# EnvironmentOnAStickV2.net
KiCad netlist of a schematic drawn in EAGLE
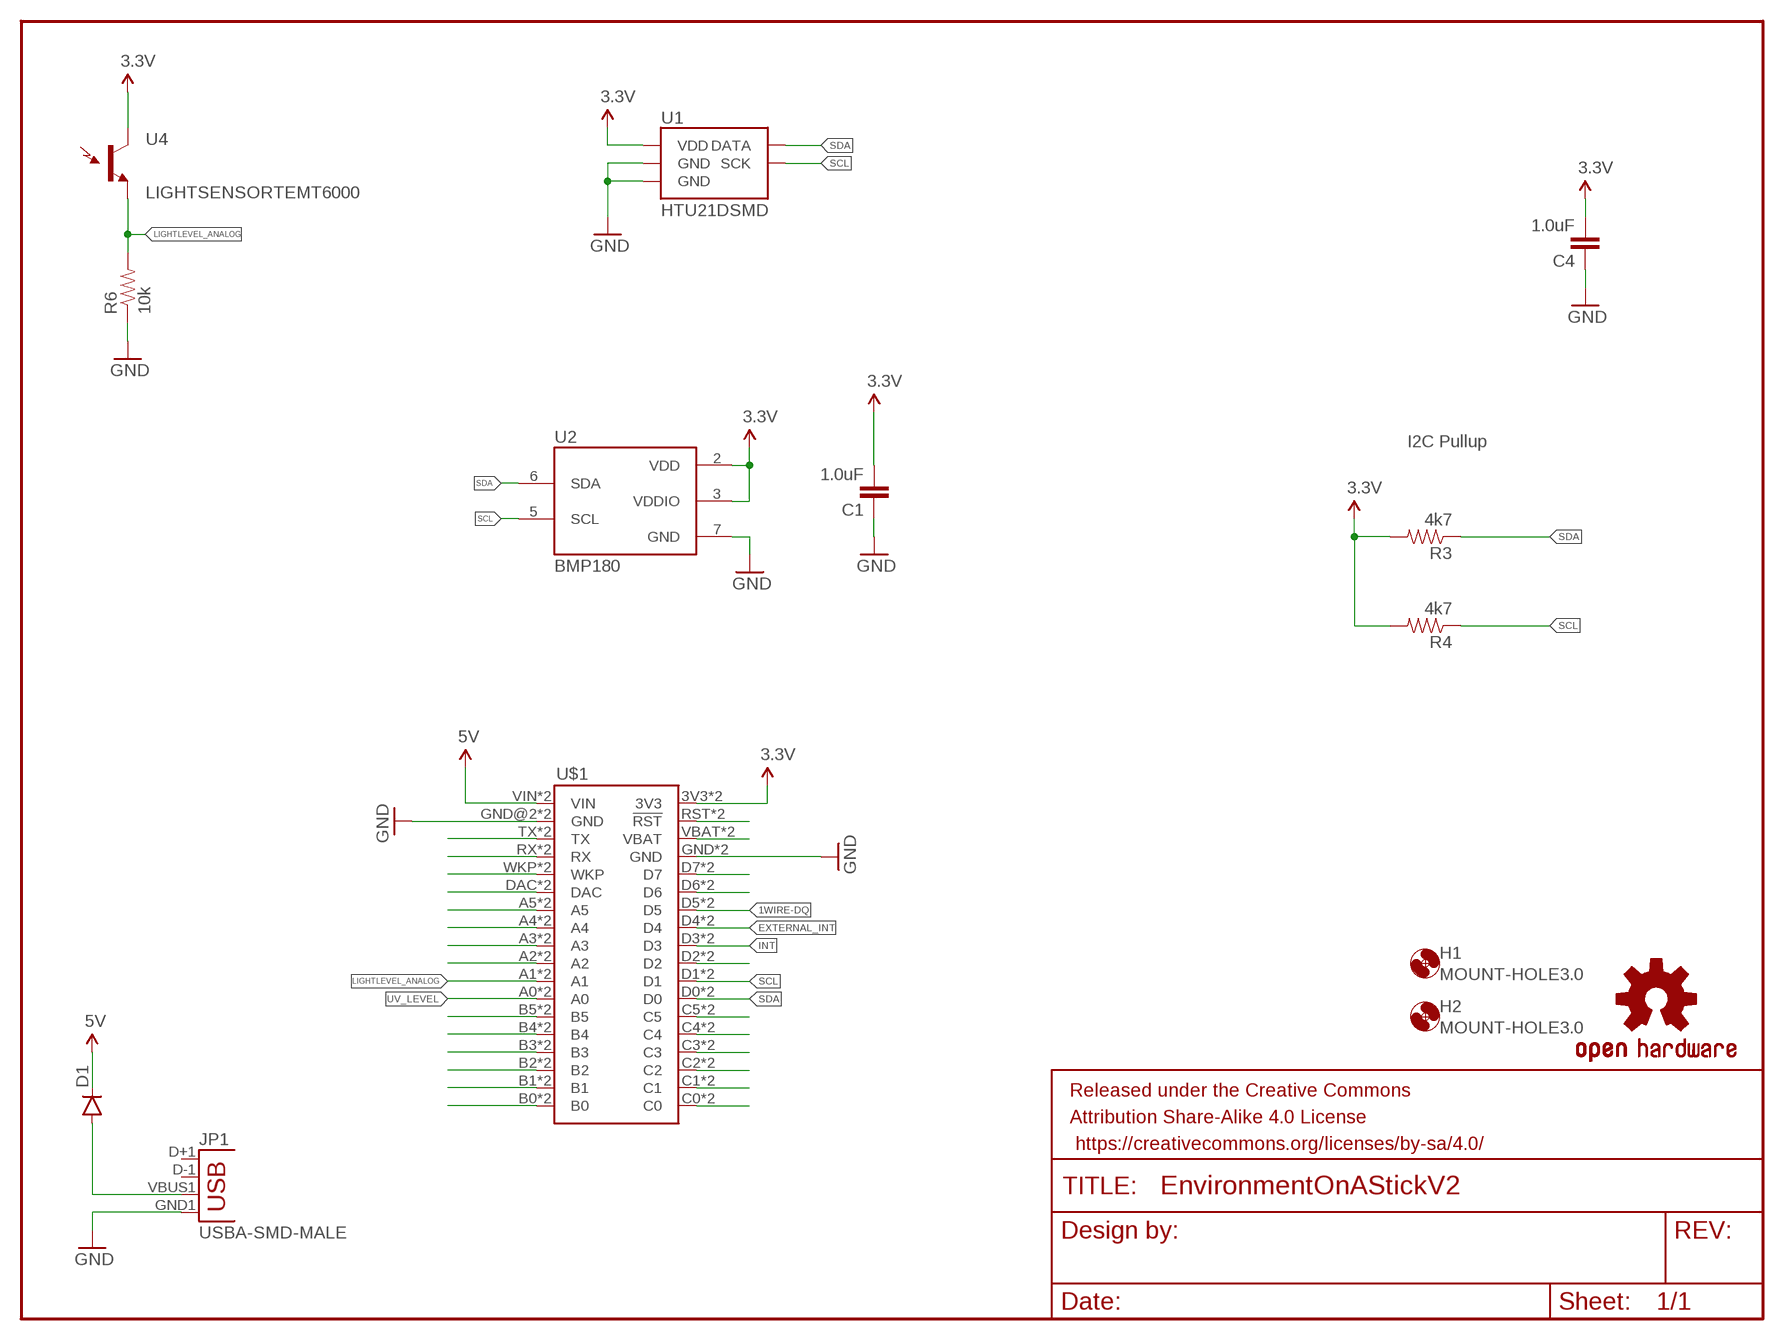
[diagram p0: schematic, sheet 1]

(export (version "E")
  (design (tool "Eeschema 10.0.6"))
  (components
    (comp (ref "C1")
      (value "1.0uF")
      (footprint "eagle-import:0805-CAP")
      (libsource (lib "eagle-import") (part "1.0UF-25V-+80/-20(0805){dblquote}"))
    )
    (comp (ref "C4")
      (value "1.0uF")
      (footprint "eagle-import:0805-CAP")
      (libsource (lib "eagle-import") (part "1.0UF-25V-+80/-20(0805){dblquote}"))
    )
    (comp (ref "D1")
      (value "DIODESMA")
      (footprint "eagle-import:SMA-DIODE")
      (libsource (lib "eagle-import") (part "DIODESMA"))
    )
    (comp (ref "FRAME1")
      (value "FRAME-LETTER")
      (footprint "eagle-import:CREATIVE_COMMONS")
      (libsource (lib "eagle-import") (part "FRAME-LETTER"))
    )
    (comp (ref "H1")
      (value "MOUNT-HOLE3.0")
      (footprint "eagle-import:3,0")
      (libsource (lib "eagle-import") (part "MOUNT-HOLE3.0"))
    )
    (comp (ref "H2")
      (value "MOUNT-HOLE3.0")
      (footprint "eagle-import:3,0")
      (libsource (lib "eagle-import") (part "MOUNT-HOLE3.0"))
    )
    (comp (ref "JP1")
      (value "USBA-SMD-MALE")
      (footprint "eagle-import:USB-A-SMT-MALE")
      (libsource (lib "eagle-import") (part "USBA-SMD-MALE"))
    )
    (comp (ref "LOGO1")
      (value "OSHW-LOGOM")
      (footprint "eagle-import:OSHW-LOGO-M")
      (libsource (lib "eagle-import") (part "OSHW-LOGOM"))
    )
    (comp (ref "R3")
      (value "4k7")
      (footprint "eagle-import:0805")
      (libsource (lib "eagle-import") (part "RESISTOR0805-RES"))
    )
    (comp (ref "R4")
      (value "4k7")
      (footprint "eagle-import:0805")
      (libsource (lib "eagle-import") (part "RESISTOR0805-RES"))
    )
    (comp (ref "R6")
      (value "10k")
      (footprint "eagle-import:0805")
      (libsource (lib "eagle-import") (part "RESISTOR0805-RES"))
    )
    (comp (ref "U$1")
      (value "ELECTRONDUALNAMED")
      (footprint "eagle-import:ELECTRON_SIMPLE_SILK_NAMES_DUAL")
      (libsource (lib "eagle-import") (part "ELECTRONDUALNAMED"))
    )
    (comp (ref "U1")
      (value "HTU21DSMD")
      (footprint "eagle-import:HTU21D")
      (libsource (lib "eagle-import") (part "HTU21DSMD"))
    )
    (comp (ref "U2")
      (value "BMP180")
      (footprint "eagle-import:BMP180")
      (libsource (lib "eagle-import") (part "BMP180"))
    )
    (comp (ref "U4")
      (value "LIGHTSENSORTEMT6000")
      (footprint "eagle-import:TEMT6000-SEN")
      (libsource (lib "eagle-import") (part "LIGHTSENSORTEMT6000"))
    )
  )
  (nets
    (net (code "1") (name "1WIRE-DQ") (class "Default")
      (node (ref "U$1") (pin "D5") (pinfunction "D5_D5") (pintype "bidirectional"))
      (node (ref "U$1") (pin "D5_1") (pinfunction "D5_D5_1") (pintype "bidirectional"))
    )
    (net (code "2") (name "3.3V") (class "Default")
      (node (ref "C1") (pin "2") (pinfunction "2_2") (pintype "passive"))
      (node (ref "C4") (pin "2") (pinfunction "2_2") (pintype "passive"))
      (node (ref "R3") (pin "2") (pinfunction "2_2") (pintype "passive"))
      (node (ref "R4") (pin "2") (pinfunction "2_2") (pintype "passive"))
      (node (ref "U$1") (pin "3V3") (pinfunction "3V3_3V3") (pintype "power_in"))
      (node (ref "U$1") (pin "3V3_1") (pinfunction "3V3_3V3_1") (pintype "power_in"))
      (node (ref "U1") (pin "VDD") (pinfunction "VDD_VDD") (pintype "power_in"))
      (node (ref "U2") (pin "2") (pinfunction "VDD_2") (pintype "power_in"))
      (node (ref "U2") (pin "3") (pinfunction "VDDIO_3") (pintype "power_in"))
      (node (ref "U4") (pin "COLLECTOR") (pinfunction "C1_COLLECTOR") (pintype "passive"))
    )
    (net (code "3") (name "5V") (class "Default")
      (node (ref "D1") (pin "C") (pinfunction "C_C") (pintype "passive"))
      (node (ref "U$1") (pin "VIN") (pinfunction "VIN_VIN") (pintype "power_in"))
      (node (ref "U$1") (pin "VIN_1B") (pinfunction "VIN_VIN_1B") (pintype "power_in"))
    )
    (net (code "4") (name "EXTERNAL_INT") (class "Default")
      (node (ref "U$1") (pin "D4") (pinfunction "D4_D4") (pintype "bidirectional"))
      (node (ref "U$1") (pin "D4_1") (pinfunction "D4_D4_1") (pintype "bidirectional"))
    )
    (net (code "5") (name "GND") (class "Default")
      (node (ref "C1") (pin "1") (pinfunction "1_1") (pintype "passive"))
      (node (ref "C4") (pin "1") (pinfunction "1_1") (pintype "passive"))
      (node (ref "JP1") (pin "GND1") (pinfunction "GND_GND1") (pintype "bidirectional"))
      (node (ref "R6") (pin "1") (pinfunction "1_1") (pintype "passive"))
      (node (ref "U$1") (pin "GND") (pinfunction "GND_GND") (pintype "power_in"))
      (node (ref "U$1") (pin "GND@2") (pinfunction "GND_GND@2") (pintype "power_in"))
      (node (ref "U$1") (pin "GND_1") (pinfunction "GND_GND_1") (pintype "power_in"))
      (node (ref "U$1") (pin "GND_1B") (pinfunction "GND_GND_1B") (pintype "power_in"))
      (node (ref "U1") (pin "7") (pinfunction "GND_7") (pintype "power_in"))
      (node (ref "U1") (pin "GND") (pinfunction "GND_GND") (pintype "power_in"))
      (node (ref "U2") (pin "7") (pinfunction "GND_7") (pintype "power_in"))
    )
    (net (code "6") (name "INT") (class "Default")
      (node (ref "U$1") (pin "D3") (pinfunction "D3_D3") (pintype "bidirectional"))
      (node (ref "U$1") (pin "D3_1") (pinfunction "D3_D3_1") (pintype "bidirectional"))
    )
    (net (code "7") (name "LIGHTLEVEL_ANALOG") (class "Default")
      (node (ref "R6") (pin "2") (pinfunction "2_2") (pintype "passive"))
      (node (ref "U$1") (pin "A1") (pinfunction "A1_A1") (pintype "bidirectional"))
      (node (ref "U$1") (pin "A1_1") (pinfunction "A1_A1_1") (pintype "bidirectional"))
      (node (ref "U4") (pin "EMITTER") (pinfunction "E1_EMITTER") (pintype "passive"))
    )
    (net (code "8") (name "Net-(JP1-VBUS)") (class "Default")
      (node (ref "D1") (pin "A") (pinfunction "A_A") (pintype "passive"))
      (node (ref "JP1") (pin "VBUS1") (pinfunction "VBUS_VBUS1") (pintype "bidirectional"))
    )
    (net (code "9") (name "Net-(U$1-A2-PadA2_1)") (class "Default")
      (node (ref "U$1") (pin "A2") (pinfunction "A2_A2") (pintype "bidirectional"))
      (node (ref "U$1") (pin "A2_1") (pinfunction "A2_A2_1") (pintype "bidirectional"))
    )
    (net (code "10") (name "Net-(U$1-A3-PadA3_1)") (class "Default")
      (node (ref "U$1") (pin "A3") (pinfunction "A3_A3") (pintype "bidirectional"))
      (node (ref "U$1") (pin "A3_1") (pinfunction "A3_A3_1") (pintype "bidirectional"))
    )
    (net (code "11") (name "Net-(U$1-A4-PadA4_1)") (class "Default")
      (node (ref "U$1") (pin "A4") (pinfunction "A4_A4") (pintype "bidirectional"))
      (node (ref "U$1") (pin "A4_1") (pinfunction "A4_A4_1") (pintype "bidirectional"))
    )
    (net (code "12") (name "Net-(U$1-A5-PadA5_1)") (class "Default")
      (node (ref "U$1") (pin "A5") (pinfunction "A5_A5") (pintype "bidirectional"))
      (node (ref "U$1") (pin "A5_1") (pinfunction "A5_A5_1") (pintype "bidirectional"))
    )
    (net (code "13") (name "Net-(U$1-B0-PadB0_1)") (class "Default")
      (node (ref "U$1") (pin "B0") (pinfunction "B0_B0") (pintype "bidirectional"))
      (node (ref "U$1") (pin "B0_1") (pinfunction "B0_B0_1") (pintype "bidirectional"))
    )
    (net (code "14") (name "Net-(U$1-B1-PadB1_1)") (class "Default")
      (node (ref "U$1") (pin "B1") (pinfunction "B1_B1") (pintype "bidirectional"))
      (node (ref "U$1") (pin "B1_1") (pinfunction "B1_B1_1") (pintype "bidirectional"))
    )
    (net (code "15") (name "Net-(U$1-B2-PadB2_1)") (class "Default")
      (node (ref "U$1") (pin "B2") (pinfunction "B2_B2") (pintype "bidirectional"))
      (node (ref "U$1") (pin "B2_1") (pinfunction "B2_B2_1") (pintype "bidirectional"))
    )
    (net (code "16") (name "Net-(U$1-B3-PadB3_1)") (class "Default")
      (node (ref "U$1") (pin "B3") (pinfunction "B3_B3") (pintype "bidirectional"))
      (node (ref "U$1") (pin "B3_1") (pinfunction "B3_B3_1") (pintype "bidirectional"))
    )
    (net (code "17") (name "Net-(U$1-B4-PadB4_1)") (class "Default")
      (node (ref "U$1") (pin "B4") (pinfunction "B4_B4") (pintype "bidirectional"))
      (node (ref "U$1") (pin "B4_1") (pinfunction "B4_B4_1") (pintype "bidirectional"))
    )
    (net (code "18") (name "Net-(U$1-B5-PadB5_1)") (class "Default")
      (node (ref "U$1") (pin "B5") (pinfunction "B5_B5") (pintype "bidirectional"))
      (node (ref "U$1") (pin "B5_1") (pinfunction "B5_B5_1") (pintype "bidirectional"))
    )
    (net (code "19") (name "Net-(U$1-C0-PadC0_1)") (class "Default")
      (node (ref "U$1") (pin "C0") (pinfunction "C0_C0") (pintype "bidirectional"))
      (node (ref "U$1") (pin "C0_1") (pinfunction "C0_C0_1") (pintype "bidirectional"))
    )
    (net (code "20") (name "Net-(U$1-C1-PadC1_1)") (class "Default")
      (node (ref "U$1") (pin "C1") (pinfunction "C1_C1") (pintype "bidirectional"))
      (node (ref "U$1") (pin "C1_1") (pinfunction "C1_C1_1") (pintype "bidirectional"))
    )
    (net (code "21") (name "Net-(U$1-C2-PadC2_1)") (class "Default")
      (node (ref "U$1") (pin "C2") (pinfunction "C2_C2") (pintype "bidirectional"))
      (node (ref "U$1") (pin "C2_1") (pinfunction "C2_C2_1") (pintype "bidirectional"))
    )
    (net (code "22") (name "Net-(U$1-C3-PadC3_1)") (class "Default")
      (node (ref "U$1") (pin "C3") (pinfunction "C3_C3") (pintype "bidirectional"))
      (node (ref "U$1") (pin "C3_1") (pinfunction "C3_C3_1") (pintype "bidirectional"))
    )
    (net (code "23") (name "Net-(U$1-C4-PadC4_1)") (class "Default")
      (node (ref "U$1") (pin "C4") (pinfunction "C4_C4") (pintype "bidirectional"))
      (node (ref "U$1") (pin "C4_1") (pinfunction "C4_C4_1") (pintype "bidirectional"))
    )
    (net (code "24") (name "Net-(U$1-C5-PadC5_1)") (class "Default")
      (node (ref "U$1") (pin "C5") (pinfunction "C5_C5") (pintype "bidirectional"))
      (node (ref "U$1") (pin "C5_1") (pinfunction "C5_C5_1") (pintype "bidirectional"))
    )
    (net (code "25") (name "Net-(U$1-D2-PadD2_1)") (class "Default")
      (node (ref "U$1") (pin "D2") (pinfunction "D2_D2") (pintype "bidirectional"))
      (node (ref "U$1") (pin "D2_1") (pinfunction "D2_D2_1") (pintype "bidirectional"))
    )
    (net (code "26") (name "Net-(U$1-D6-PadD6_1)") (class "Default")
      (node (ref "U$1") (pin "D6") (pinfunction "D6_D6") (pintype "bidirectional"))
      (node (ref "U$1") (pin "D6_1") (pinfunction "D6_D6_1") (pintype "bidirectional"))
    )
    (net (code "27") (name "Net-(U$1-D7-PadD7_1)") (class "Default")
      (node (ref "U$1") (pin "D7") (pinfunction "D7_D7") (pintype "bidirectional"))
      (node (ref "U$1") (pin "D7_1") (pinfunction "D7_D7_1") (pintype "bidirectional"))
    )
    (net (code "28") (name "Net-(U$1-DAC-PadDAC_1)") (class "Default")
      (node (ref "U$1") (pin "DAC") (pinfunction "DAC_DAC") (pintype "bidirectional"))
      (node (ref "U$1") (pin "DAC_1") (pinfunction "DAC_DAC_1") (pintype "bidirectional"))
    )
    (net (code "29") (name "Net-(U$1-PadRX)") (class "Default")
      (node (ref "U$1") (pin "RX") (pinfunction "RX_RX") (pintype "bidirectional"))
      (node (ref "U$1") (pin "RX_1") (pinfunction "RX_RX_1") (pintype "bidirectional"))
    )
    (net (code "30") (name "Net-(U$1-PadTX)") (class "Default")
      (node (ref "U$1") (pin "TX") (pinfunction "TX_TX") (pintype "bidirectional"))
      (node (ref "U$1") (pin "TX_1") (pinfunction "TX_TX_1") (pintype "bidirectional"))
    )
    (net (code "31") (name "Net-(U$1-PadVBAT)") (class "Default")
      (node (ref "U$1") (pin "VBAT") (pinfunction "VBAT_VBAT") (pintype "passive"))
      (node (ref "U$1") (pin "VBATT_1") (pinfunction "VBAT_VBATT_1") (pintype "passive"))
    )
    (net (code "32") (name "Net-(U$1-PadWKP)") (class "Default")
      (node (ref "U$1") (pin "WKP") (pinfunction "WKP_WKP") (pintype "bidirectional"))
      (node (ref "U$1") (pin "WKP_1") (pinfunction "WKP_WKP_1") (pintype "bidirectional"))
    )
    (net (code "33") (name "Net-(U$1-~{RST}-PadRST)") (class "Default")
      (node (ref "U$1") (pin "RST") (pinfunction "~{RST}_RST") (pintype "bidirectional"))
      (node (ref "U$1") (pin "RST_1") (pinfunction "~{RST}_RST_1") (pintype "bidirectional"))
    )
    (net (code "34") (name "SCL") (class "Default")
      (node (ref "R4") (pin "1") (pinfunction "1_1") (pintype "passive"))
      (node (ref "U$1") (pin "D1") (pinfunction "D1_D1") (pintype "bidirectional"))
      (node (ref "U$1") (pin "D1_1") (pinfunction "D1_D1_1") (pintype "bidirectional"))
      (node (ref "U1") (pin "SCK") (pinfunction "SCK_SCK") (pintype "input"))
      (node (ref "U2") (pin "5") (pinfunction "SCL_5") (pintype "input"))
    )
    (net (code "35") (name "SDA") (class "Default")
      (node (ref "R3") (pin "1") (pinfunction "1_1") (pintype "passive"))
      (node (ref "U$1") (pin "D0") (pinfunction "D0_D0") (pintype "bidirectional"))
      (node (ref "U$1") (pin "D0_1") (pinfunction "D0_D0_1") (pintype "bidirectional"))
      (node (ref "U1") (pin "DATA") (pinfunction "DATA_DATA") (pintype "bidirectional"))
      (node (ref "U2") (pin "6") (pinfunction "SDA_6") (pintype "bidirectional"))
    )
    (net (code "36") (name "UV_LEVEL") (class "Default")
      (node (ref "U$1") (pin "A0") (pinfunction "A0_A0") (pintype "bidirectional"))
      (node (ref "U$1") (pin "A0_1") (pinfunction "A0_A0_1") (pintype "bidirectional"))
    )
    (net (code "37") (name "unconnected-(JP1-D+-PadD+1)") (class "Default")
      (node (ref "JP1") (pin "D+1") (pinfunction "D+_D+1") (pintype "bidirectional"))
    )
    (net (code "38") (name "unconnected-(JP1-D--PadD-1)") (class "Default")
      (node (ref "JP1") (pin "D-1") (pinfunction "D-_D-1") (pintype "bidirectional"))
    )
  )
)
